# wrt54_relay_board.net
KiCad netlist of a schematic drawn in EAGLE
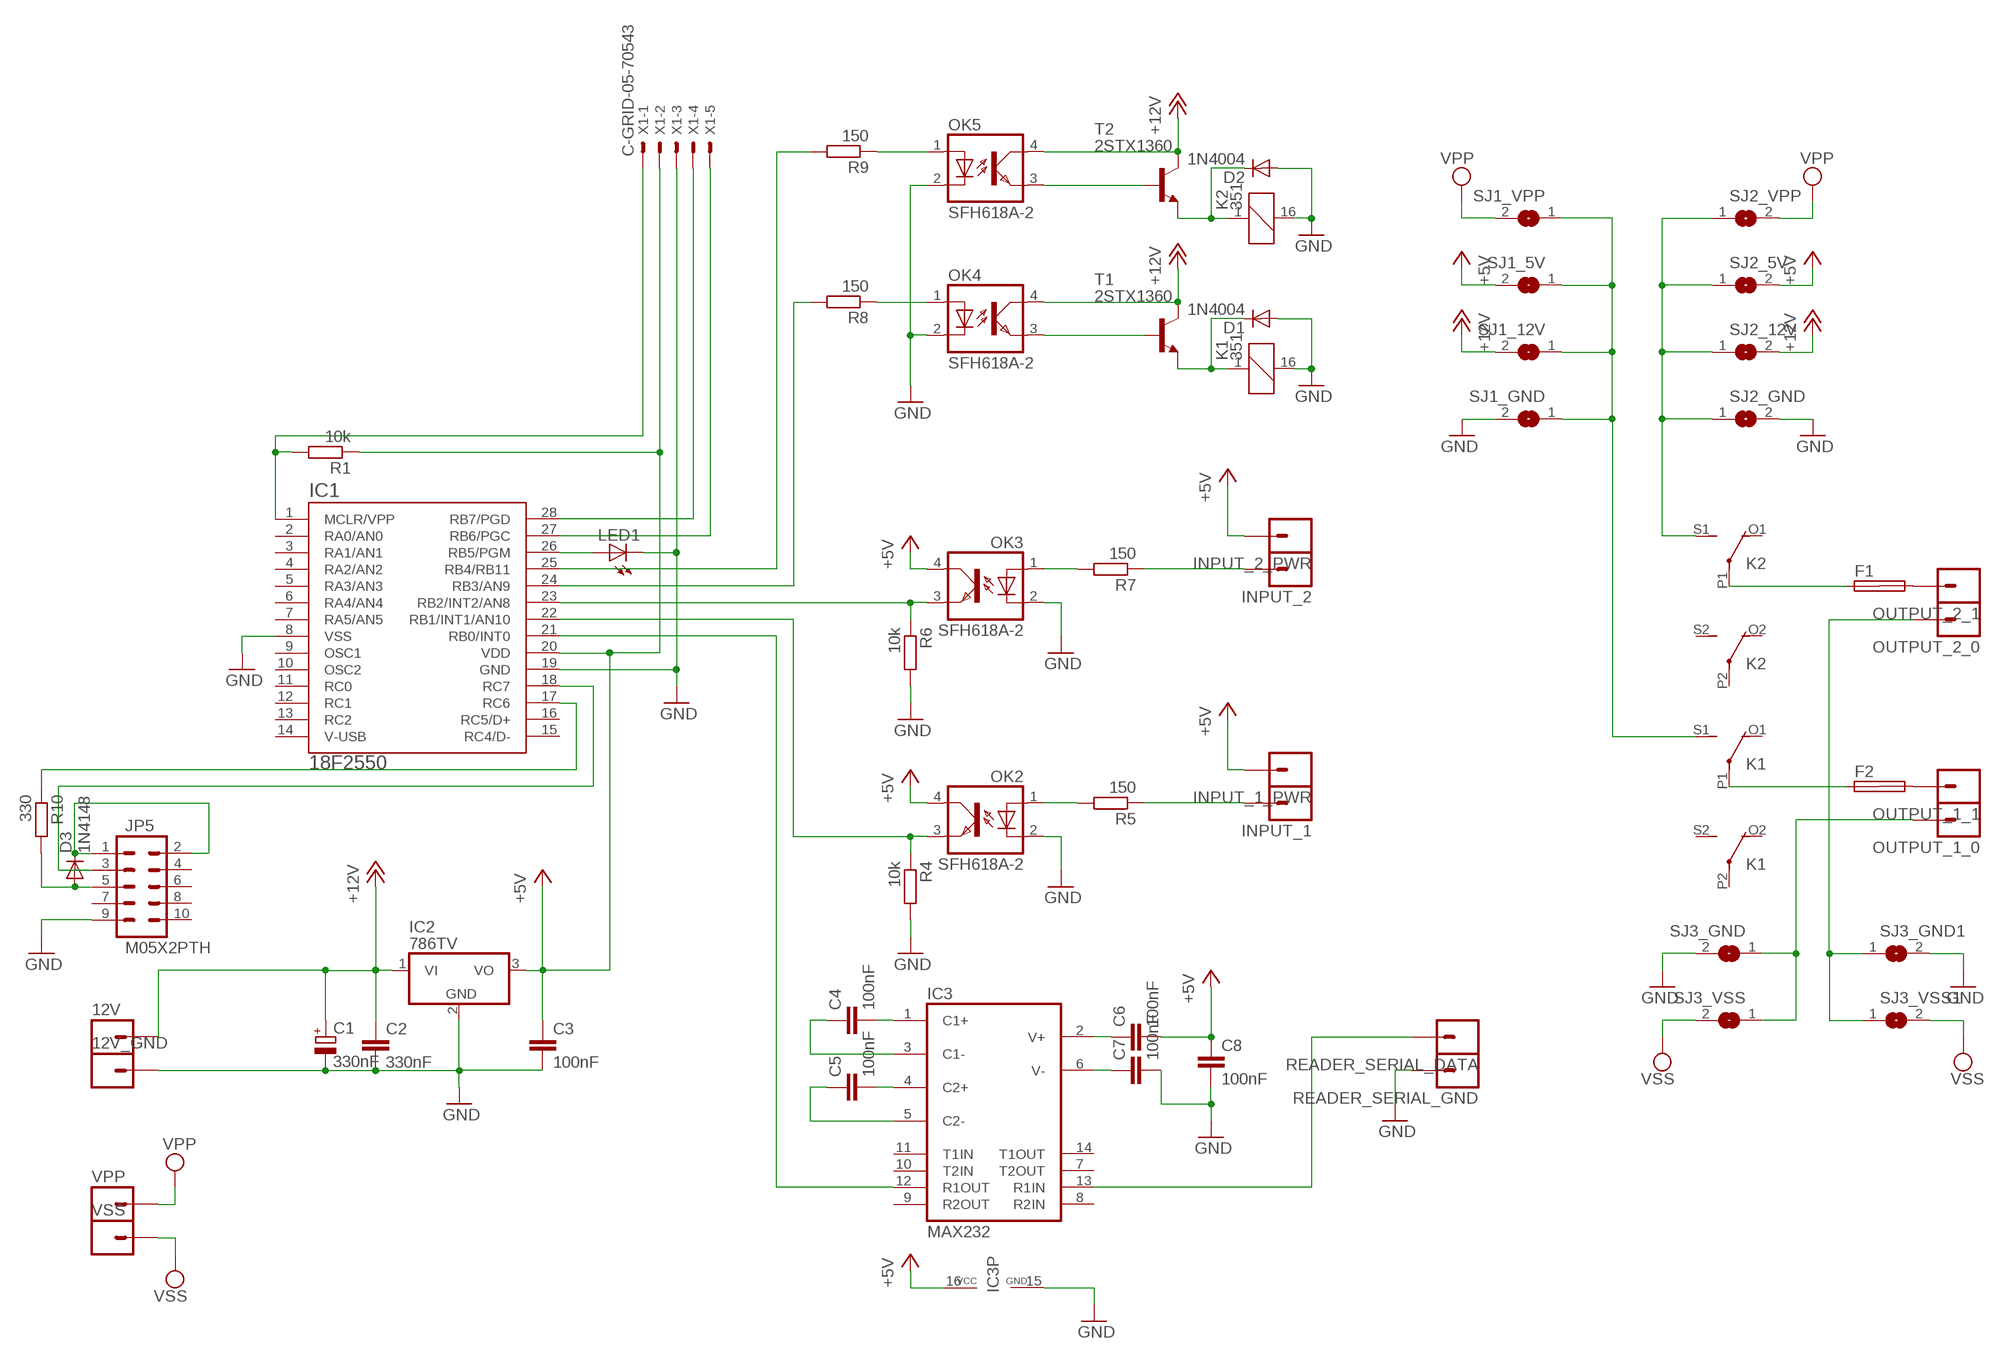
[diagram p0: schematic, sheet 1]

(export (version "E")
  (design (tool "Eeschema 10.0.6"))
  (components
    (comp (ref "12V")
      (value "M01PTH_LONGPAD")
      (footprint "eagle-import:1X01_LONGPAD")
      (libsource (lib "eagle-import") (part "M01PTH_LONGPAD"))
    )
    (comp (ref "12V_GND")
      (value "M01PTH_LONGPAD")
      (footprint "eagle-import:1X01_LONGPAD")
      (libsource (lib "eagle-import") (part "M01PTH_LONGPAD"))
    )
    (comp (ref "C1")
      (value "330nF")
      (footprint "eagle-import:E5-6")
      (libsource (lib "eagle-import") (part "CPOL-EUE5-6"))
    )
    (comp (ref "C2")
      (value "330nF")
      (footprint "eagle-import:C5B2.5")
      (libsource (lib "eagle-import") (part "C5/2.5"))
    )
    (comp (ref "C3")
      (value "100nF")
      (footprint "eagle-import:C5B2.5")
      (libsource (lib "eagle-import") (part "C5/2.5"))
    )
    (comp (ref "C4")
      (value "100nF")
      (footprint "eagle-import:C5B2.5")
      (libsource (lib "eagle-import") (part "C5/2.5"))
    )
    (comp (ref "C5")
      (value "100nF")
      (footprint "eagle-import:C5B2.5")
      (libsource (lib "eagle-import") (part "C5/2.5"))
    )
    (comp (ref "C6")
      (value "100nF")
      (footprint "eagle-import:C5B2.5")
      (libsource (lib "eagle-import") (part "C5/2.5"))
    )
    (comp (ref "C7")
      (value "100nF")
      (footprint "eagle-import:C5B2.5")
      (libsource (lib "eagle-import") (part "C5/2.5"))
    )
    (comp (ref "C8")
      (value "100nF")
      (footprint "eagle-import:C5B2.5")
      (libsource (lib "eagle-import") (part "C5/2.5"))
    )
    (comp (ref "D1")
      (value "1N4004")
      (footprint "eagle-import:DO35-7")
      (libsource (lib "eagle-import") (part "1N4148DO35-7"))
    )
    (comp (ref "D2")
      (value "1N4004")
      (footprint "eagle-import:DO35-7")
      (libsource (lib "eagle-import") (part "1N4148DO35-7"))
    )
    (comp (ref "D3")
      (value "1N4148")
      (footprint "eagle-import:DO35-7")
      (libsource (lib "eagle-import") (part "1N4148DO35-7"))
    )
    (comp (ref "F1")
      (value "SHK20L")
      (footprint "eagle-import:SHK20L")
      (libsource (lib "eagle-import") (part "SHK20L"))
    )
    (comp (ref "F2")
      (value "SHK20L")
      (footprint "eagle-import:SHK20L")
      (libsource (lib "eagle-import") (part "SHK20L"))
    )
    (comp (ref "IC1")
      (value "18F2550")
      (footprint "eagle-import:DIL28")
      (libsource (lib "eagle-import") (part "PIC18F2550DIL-28"))
    )
    (comp (ref "IC2")
      (value "786TV")
      (footprint "eagle-import:TO220V")
      (libsource (lib "eagle-import") (part "78TV6"))
    )
    (comp (ref "IC3")
      (value "MAX232")
      (footprint "eagle-import:DIL16")
      (fields (field (name "MF") "MAXIM") (field (name "MPN") "MAX232ACPE+"))
      (libsource (lib "eagle-import") (part "MAX232"))
    )
    (comp (ref "INPUT_1")
      (value "M01PTH_LONGPAD")
      (footprint "eagle-import:1X01_LONGPAD")
      (libsource (lib "eagle-import") (part "M01PTH_LONGPAD"))
    )
    (comp (ref "INPUT_1_PWR")
      (value "M01PTH_LONGPAD")
      (footprint "eagle-import:1X01_LONGPAD")
      (libsource (lib "eagle-import") (part "M01PTH_LONGPAD"))
    )
    (comp (ref "INPUT_2")
      (value "M01PTH_LONGPAD")
      (footprint "eagle-import:1X01_LONGPAD")
      (libsource (lib "eagle-import") (part "M01PTH_LONGPAD"))
    )
    (comp (ref "INPUT_2_PWR")
      (value "M01PTH_LONGPAD")
      (footprint "eagle-import:1X01_LONGPAD")
      (libsource (lib "eagle-import") (part "M01PTH_LONGPAD"))
    )
    (comp (ref "JP5")
      (value "M05X2PTH")
      (footprint "eagle-import:AVR_ICSP")
      (libsource (lib "eagle-import") (part "M05X2PTH"))
    )
    (comp (ref "K1")
      (value "351")
      (footprint "eagle-import:351")
      (libsource (lib "eagle-import") (part "351"))
    )
    (comp (ref "K2")
      (value "351")
      (footprint "eagle-import:351")
      (libsource (lib "eagle-import") (part "351"))
    )
    (comp (ref "LED1")
      (value "LED5MM")
      (footprint "eagle-import:LED5MM")
      (libsource (lib "eagle-import") (part "LED5MM"))
    )
    (comp (ref "OK2")
      (value "SFH618A-2")
      (footprint "eagle-import:DIP4")
      (libsource (lib "eagle-import") (part "SFH618?A-2"))
    )
    (comp (ref "OK3")
      (value "SFH618A-2")
      (footprint "eagle-import:DIP4")
      (libsource (lib "eagle-import") (part "SFH618?A-2"))
    )
    (comp (ref "OK4")
      (value "SFH618A-2")
      (footprint "eagle-import:DIP4")
      (libsource (lib "eagle-import") (part "SFH618?A-2"))
    )
    (comp (ref "OK5")
      (value "SFH618A-2")
      (footprint "eagle-import:DIP4")
      (libsource (lib "eagle-import") (part "SFH618?A-2"))
    )
    (comp (ref "OUTPUT_1_0")
      (value "M01PTH_LONGPAD")
      (footprint "eagle-import:1X01_LONGPAD")
      (libsource (lib "eagle-import") (part "M01PTH_LONGPAD"))
    )
    (comp (ref "OUTPUT_1_1")
      (value "M01PTH_LONGPAD")
      (footprint "eagle-import:1X01_LONGPAD")
      (libsource (lib "eagle-import") (part "M01PTH_LONGPAD"))
    )
    (comp (ref "OUTPUT_2_0")
      (value "M01PTH_LONGPAD")
      (footprint "eagle-import:1X01_LONGPAD")
      (libsource (lib "eagle-import") (part "M01PTH_LONGPAD"))
    )
    (comp (ref "OUTPUT_2_1")
      (value "M01PTH_LONGPAD")
      (footprint "eagle-import:1X01_LONGPAD")
      (libsource (lib "eagle-import") (part "M01PTH_LONGPAD"))
    )
    (comp (ref "R1")
      (value "10k")
      (footprint "eagle-import:0204_7")
      (libsource (lib "eagle-import") (part "R-EU_0204/7"))
    )
    (comp (ref "R4")
      (value "10k")
      (footprint "eagle-import:0207_10")
      (libsource (lib "eagle-import") (part "R-EU_0207/10"))
    )
    (comp (ref "R5")
      (value "150")
      (footprint "eagle-import:0204V")
      (libsource (lib "eagle-import") (part "R-EU_0204/2V"))
    )
    (comp (ref "R6")
      (value "10k")
      (footprint "eagle-import:0207_10")
      (libsource (lib "eagle-import") (part "R-EU_0207/10"))
    )
    (comp (ref "R7")
      (value "150")
      (footprint "eagle-import:0204V")
      (libsource (lib "eagle-import") (part "R-EU_0204/2V"))
    )
    (comp (ref "R8")
      (value "150")
      (footprint "eagle-import:0204_7")
      (libsource (lib "eagle-import") (part "R-EU_0204/7"))
    )
    (comp (ref "R9")
      (value "150")
      (footprint "eagle-import:0204_7")
      (libsource (lib "eagle-import") (part "R-EU_0204/7"))
    )
    (comp (ref "R10")
      (value "330")
      (footprint "eagle-import:0204V")
      (libsource (lib "eagle-import") (part "R-EU_0204/2V"))
    )
    (comp (ref "READER_SERIAL_DATA")
      (value "M01PTH_LONGPAD")
      (footprint "eagle-import:1X01_LONGPAD")
      (libsource (lib "eagle-import") (part "M01PTH_LONGPAD"))
    )
    (comp (ref "READER_SERIAL_GND")
      (value "M01PTH_LONGPAD")
      (footprint "eagle-import:1X01_LONGPAD")
      (libsource (lib "eagle-import") (part "M01PTH_LONGPAD"))
    )
    (comp (ref "SJ1_5V")
      (value "SJW")
      (footprint "eagle-import:SJW")
      (libsource (lib "eagle-import") (part "SJW"))
    )
    (comp (ref "SJ1_12V")
      (value "SJW")
      (footprint "eagle-import:SJW")
      (libsource (lib "eagle-import") (part "SJW"))
    )
    (comp (ref "SJ1_GND")
      (value "SJW")
      (footprint "eagle-import:SJW")
      (libsource (lib "eagle-import") (part "SJW"))
    )
    (comp (ref "SJ1_VPP")
      (value "SJW")
      (footprint "eagle-import:SJW")
      (libsource (lib "eagle-import") (part "SJW"))
    )
    (comp (ref "SJ2_5V")
      (value "SJW")
      (footprint "eagle-import:SJW")
      (libsource (lib "eagle-import") (part "SJW"))
    )
    (comp (ref "SJ2_12V")
      (value "SJW")
      (footprint "eagle-import:SJW")
      (libsource (lib "eagle-import") (part "SJW"))
    )
    (comp (ref "SJ2_GND")
      (value "SJW")
      (footprint "eagle-import:SJW")
      (libsource (lib "eagle-import") (part "SJW"))
    )
    (comp (ref "SJ2_VPP")
      (value "SJW")
      (footprint "eagle-import:SJW")
      (libsource (lib "eagle-import") (part "SJW"))
    )
    (comp (ref "SJ3_GND")
      (value "SJW")
      (footprint "eagle-import:SJW")
      (libsource (lib "eagle-import") (part "SJW"))
    )
    (comp (ref "SJ3_GND1")
      (value "SJW")
      (footprint "eagle-import:SJW")
      (libsource (lib "eagle-import") (part "SJW"))
    )
    (comp (ref "SJ3_VSS")
      (value "SJW")
      (footprint "eagle-import:SJW")
      (libsource (lib "eagle-import") (part "SJW"))
    )
    (comp (ref "SJ3_VSS1")
      (value "SJW")
      (footprint "eagle-import:SJW")
      (libsource (lib "eagle-import") (part "SJW"))
    )
    (comp (ref "T1")
      (value "2STX1360")
      (footprint "eagle-import:TO92-ECB")
      (libsource (lib "eagle-import") (part "2SC1740"))
    )
    (comp (ref "T2")
      (value "2STX1360")
      (footprint "eagle-import:TO92-ECB")
      (libsource (lib "eagle-import") (part "2SC1740"))
    )
    (comp (ref "VPP")
      (value "M01PTH_LONGPAD")
      (footprint "eagle-import:1X01_LONGPAD")
      (libsource (lib "eagle-import") (part "M01PTH_LONGPAD"))
    )
    (comp (ref "VSS")
      (value "M01PTH_LONGPAD")
      (footprint "eagle-import:1X01_LONGPAD")
      (libsource (lib "eagle-import") (part "M01PTH_LONGPAD"))
    )
    (comp (ref "X1")
      (value "C-GRID-05-70543")
      (footprint "eagle-import:70543-05")
      (libsource (lib "eagle-import") (part "C-GRID-05-70543"))
    )
  )
  (nets
    (net (code "1") (name "+5V") (class "Default")
      (node (ref "C3") (pin "1") (pinfunction "1_1") (pintype "passive"))
      (node (ref "C6") (pin "2") (pinfunction "2_2") (pintype "passive"))
      (node (ref "C8") (pin "1") (pinfunction "1_1") (pintype "passive"))
      (node (ref "IC1") (pin "20") (pinfunction "VDD_20") (pintype "bidirectional"))
      (node (ref "IC2") (pin "3") (pinfunction "VO_3") (pintype "passive"))
      (node (ref "IC3") (pin "16") (pinfunction "VCC_16") (pintype "power_in"))
      (node (ref "INPUT_1_PWR") (pin "1") (pinfunction "1_1") (pintype "passive"))
      (node (ref "INPUT_2_PWR") (pin "1") (pinfunction "1_1") (pintype "passive"))
      (node (ref "OK2") (pin "4") (pinfunction "COL_4") (pintype "passive"))
      (node (ref "OK3") (pin "4") (pinfunction "COL_4") (pintype "passive"))
      (node (ref "R1") (pin "1") (pinfunction "1_1") (pintype "passive"))
      (node (ref "SJ1_5V") (pin "2") (pinfunction "2_2") (pintype "passive"))
      (node (ref "SJ2_5V") (pin "2") (pinfunction "2_2") (pintype "passive"))
      (node (ref "X1") (pin "2") (pinfunction "S_2") (pintype "passive"))
    )
    (net (code "2") (name "+12V") (class "Default")
      (node (ref "12V") (pin "1") (pinfunction "1_1") (pintype "passive"))
      (node (ref "C1") (pin "+") (pinfunction "+_+") (pintype "passive"))
      (node (ref "C2") (pin "1") (pinfunction "1_1") (pintype "passive"))
      (node (ref "IC2") (pin "1") (pinfunction "VI_1") (pintype "input"))
      (node (ref "OK4") (pin "4") (pinfunction "COL_4") (pintype "passive"))
      (node (ref "OK5") (pin "4") (pinfunction "COL_4") (pintype "passive"))
      (node (ref "SJ1_12V") (pin "2") (pinfunction "2_2") (pintype "passive"))
      (node (ref "SJ2_12V") (pin "2") (pinfunction "2_2") (pintype "passive"))
      (node (ref "T1") (pin "C") (pinfunction "C_C") (pintype "passive"))
      (node (ref "T2") (pin "C") (pinfunction "C_C") (pintype "passive"))
    )
    (net (code "3") (name "GND") (class "Default")
      (node (ref "12V_GND") (pin "1") (pinfunction "1_1") (pintype "passive"))
      (node (ref "C1") (pin "-") (pinfunction "-_-") (pintype "passive"))
      (node (ref "C2") (pin "2") (pinfunction "2_2") (pintype "passive"))
      (node (ref "C3") (pin "2") (pinfunction "2_2") (pintype "passive"))
      (node (ref "C7") (pin "2") (pinfunction "2_2") (pintype "passive"))
      (node (ref "C8") (pin "2") (pinfunction "2_2") (pintype "passive"))
      (node (ref "D1") (pin "A") (pinfunction "A_A") (pintype "passive"))
      (node (ref "D2") (pin "A") (pinfunction "A_A") (pintype "passive"))
      (node (ref "IC1") (pin "19") (pinfunction "GND_19") (pintype "bidirectional"))
      (node (ref "IC1") (pin "8") (pinfunction "VSS_8") (pintype "bidirectional"))
      (node (ref "IC2") (pin "2") (pinfunction "GND_2") (pintype "passive"))
      (node (ref "IC3") (pin "15") (pinfunction "GND_15") (pintype "power_in"))
      (node (ref "JP5") (pin "9") (pinfunction "9_9") (pintype "passive"))
      (node (ref "K1") (pin "16") (pinfunction "2_16") (pintype "passive"))
      (node (ref "K2") (pin "16") (pinfunction "2_16") (pintype "passive"))
      (node (ref "LED1") (pin "K") (pinfunction "C_K") (pintype "passive"))
      (node (ref "OK2") (pin "2") (pinfunction "C_2") (pintype "passive"))
      (node (ref "OK3") (pin "2") (pinfunction "C_2") (pintype "passive"))
      (node (ref "OK4") (pin "2") (pinfunction "C_2") (pintype "passive"))
      (node (ref "OK5") (pin "2") (pinfunction "C_2") (pintype "passive"))
      (node (ref "R4") (pin "2") (pinfunction "2_2") (pintype "passive"))
      (node (ref "R6") (pin "2") (pinfunction "2_2") (pintype "passive"))
      (node (ref "READER_SERIAL_GND") (pin "1") (pinfunction "1_1") (pintype "passive"))
      (node (ref "SJ1_GND") (pin "2") (pinfunction "2_2") (pintype "passive"))
      (node (ref "SJ2_GND") (pin "2") (pinfunction "2_2") (pintype "passive"))
      (node (ref "SJ3_GND") (pin "2") (pinfunction "2_2") (pintype "passive"))
      (node (ref "SJ3_GND1") (pin "2") (pinfunction "2_2") (pintype "passive"))
      (node (ref "X1") (pin "3") (pinfunction "S_3") (pintype "passive"))
    )
    (net (code "4") (name "Net-(D1-PadC)") (class "Default")
      (node (ref "D1") (pin "C") (pinfunction "C_C") (pintype "passive"))
      (node (ref "K1") (pin "1") (pinfunction "1_1") (pintype "passive"))
      (node (ref "T1") (pin "E") (pinfunction "E_E") (pintype "passive"))
    )
    (net (code "5") (name "Net-(D2-PadC)") (class "Default")
      (node (ref "D2") (pin "C") (pinfunction "C_C") (pintype "passive"))
      (node (ref "K2") (pin "1") (pinfunction "1_1") (pintype "passive"))
      (node (ref "T2") (pin "E") (pinfunction "E_E") (pintype "passive"))
    )
    (net (code "6") (name "Net-(D3-PadA)") (class "Default")
      (node (ref "D3") (pin "A") (pinfunction "A_A") (pintype "passive"))
      (node (ref "JP5") (pin "5") (pinfunction "5_5") (pintype "passive"))
      (node (ref "R10") (pin "2") (pinfunction "2_2") (pintype "passive"))
    )
    (net (code "7") (name "Net-(D3-PadC)") (class "Default")
      (node (ref "D3") (pin "C") (pinfunction "C_C") (pintype "passive"))
      (node (ref "JP5") (pin "1") (pinfunction "1_1") (pintype "passive"))
      (node (ref "JP5") (pin "2") (pinfunction "2_2") (pintype "passive"))
    )
    (net (code "8") (name "Net-(F1-Pad2A)") (class "Default")
      (node (ref "F1") (pin "2A") (pinfunction "2A_2A") (pintype "passive"))
      (node (ref "OUTPUT_2_1") (pin "1") (pinfunction "1_1") (pintype "passive"))
    )
    (net (code "9") (name "Net-(F2-Pad2A)") (class "Default")
      (node (ref "F2") (pin "2A") (pinfunction "2A_2A") (pintype "passive"))
      (node (ref "OUTPUT_1_1") (pin "1") (pinfunction "1_1") (pintype "passive"))
    )
    (net (code "10") (name "Net-(IC1-MCLR{slash}VPP)") (class "Default")
      (node (ref "IC1") (pin "1") (pinfunction "MCLR/VPP_1") (pintype "bidirectional"))
      (node (ref "R1") (pin "2") (pinfunction "2_2") (pintype "passive"))
      (node (ref "X1") (pin "1") (pinfunction "S_1") (pintype "passive"))
    )
    (net (code "11") (name "Net-(IC1-RB0{slash}INT0)") (class "Default")
      (node (ref "IC1") (pin "21") (pinfunction "RB0/INT0_21") (pintype "bidirectional"))
      (node (ref "IC3") (pin "12") (pinfunction "R1OUT_12") (pintype "output"))
    )
    (net (code "12") (name "Net-(IC1-RB1{slash}INT1{slash}AN10)") (class "Default")
      (node (ref "IC1") (pin "22") (pinfunction "RB1/INT1/AN10_22") (pintype "bidirectional"))
      (node (ref "OK2") (pin "3") (pinfunction "EMIT_3") (pintype "passive"))
      (node (ref "R4") (pin "1") (pinfunction "1_1") (pintype "passive"))
    )
    (net (code "13") (name "Net-(IC1-RB2{slash}INT2{slash}AN8)") (class "Default")
      (node (ref "IC1") (pin "23") (pinfunction "RB2/INT2/AN8_23") (pintype "bidirectional"))
      (node (ref "OK3") (pin "3") (pinfunction "EMIT_3") (pintype "passive"))
      (node (ref "R6") (pin "1") (pinfunction "1_1") (pintype "passive"))
    )
    (net (code "14") (name "Net-(IC1-RB3{slash}AN9)") (class "Default")
      (node (ref "IC1") (pin "24") (pinfunction "RB3/AN9_24") (pintype "bidirectional"))
      (node (ref "R8") (pin "2") (pinfunction "2_2") (pintype "passive"))
    )
    (net (code "15") (name "Net-(IC1-RB4{slash}RB11)") (class "Default")
      (node (ref "IC1") (pin "25") (pinfunction "RB4/RB11_25") (pintype "bidirectional"))
      (node (ref "R9") (pin "2") (pinfunction "2_2") (pintype "passive"))
    )
    (net (code "16") (name "Net-(IC1-RB5{slash}PGM)") (class "Default")
      (node (ref "IC1") (pin "26") (pinfunction "RB5/PGM_26") (pintype "bidirectional"))
      (node (ref "LED1") (pin "A") (pinfunction "A_A") (pintype "passive"))
    )
    (net (code "17") (name "Net-(IC1-RB6{slash}PGC)") (class "Default")
      (node (ref "IC1") (pin "27") (pinfunction "RB6/PGC_27") (pintype "bidirectional"))
      (node (ref "X1") (pin "5") (pinfunction "S_5") (pintype "passive"))
    )
    (net (code "18") (name "Net-(IC1-RB7{slash}PGD)") (class "Default")
      (node (ref "IC1") (pin "28") (pinfunction "RB7/PGD_28") (pintype "bidirectional"))
      (node (ref "X1") (pin "4") (pinfunction "S_4") (pintype "passive"))
    )
    (net (code "19") (name "Net-(IC1-RC6)") (class "Default")
      (node (ref "IC1") (pin "17") (pinfunction "RC6_17") (pintype "bidirectional"))
      (node (ref "R10") (pin "1") (pinfunction "1_1") (pintype "passive"))
    )
    (net (code "20") (name "Net-(IC1-RC7)") (class "Default")
      (node (ref "IC1") (pin "18") (pinfunction "RC7_18") (pintype "bidirectional"))
      (node (ref "JP5") (pin "3") (pinfunction "3_3") (pintype "passive"))
    )
    (net (code "21") (name "Net-(IC3A-C1+)") (class "Default")
      (node (ref "C4") (pin "2") (pinfunction "2_2") (pintype "passive"))
      (node (ref "IC3") (pin "1") (pinfunction "C1+_1") (pintype "bidirectional"))
    )
    (net (code "22") (name "Net-(IC3A-C1-)") (class "Default")
      (node (ref "C4") (pin "1") (pinfunction "1_1") (pintype "passive"))
      (node (ref "IC3") (pin "3") (pinfunction "C1-_3") (pintype "bidirectional"))
    )
    (net (code "23") (name "Net-(IC3A-C2+)") (class "Default")
      (node (ref "C5") (pin "2") (pinfunction "2_2") (pintype "passive"))
      (node (ref "IC3") (pin "4") (pinfunction "C2+_4") (pintype "bidirectional"))
    )
    (net (code "24") (name "Net-(IC3A-C2-)") (class "Default")
      (node (ref "C5") (pin "1") (pinfunction "1_1") (pintype "passive"))
      (node (ref "IC3") (pin "5") (pinfunction "C2-_5") (pintype "bidirectional"))
    )
    (net (code "25") (name "Net-(IC3A-R1IN)") (class "Default")
      (node (ref "IC3") (pin "13") (pinfunction "R1IN_13") (pintype "input"))
      (node (ref "READER_SERIAL_DATA") (pin "1") (pinfunction "1_1") (pintype "passive"))
    )
    (net (code "26") (name "Net-(IC3A-V+)") (class "Default")
      (node (ref "C6") (pin "1") (pinfunction "1_1") (pintype "passive"))
      (node (ref "IC3") (pin "2") (pinfunction "V+_2") (pintype "bidirectional"))
    )
    (net (code "27") (name "Net-(IC3A-V-)") (class "Default")
      (node (ref "C7") (pin "1") (pinfunction "1_1") (pintype "passive"))
      (node (ref "IC3") (pin "6") (pinfunction "V-_6") (pintype "bidirectional"))
    )
    (net (code "28") (name "Net-(INPUT_1-Pad1)") (class "Default")
      (node (ref "INPUT_1") (pin "1") (pinfunction "1_1") (pintype "passive"))
      (node (ref "R5") (pin "1") (pinfunction "1_1") (pintype "passive"))
    )
    (net (code "29") (name "Net-(INPUT_2-Pad1)") (class "Default")
      (node (ref "INPUT_2") (pin "1") (pinfunction "1_1") (pintype "passive"))
      (node (ref "R7") (pin "1") (pinfunction "1_1") (pintype "passive"))
    )
    (net (code "30") (name "Net-(K1B-P)") (class "Default")
      (node (ref "F2") (pin "1A") (pinfunction "1A_1A") (pintype "passive"))
      (node (ref "K1") (pin "P1") (pinfunction "P_P1") (pintype "passive"))
    )
    (net (code "31") (name "Net-(K1B-S)") (class "Default")
      (node (ref "K1") (pin "S1") (pinfunction "S_S1") (pintype "passive"))
      (node (ref "SJ1_12V") (pin "1") (pinfunction "1_1") (pintype "passive"))
      (node (ref "SJ1_5V") (pin "1") (pinfunction "1_1") (pintype "passive"))
      (node (ref "SJ1_GND") (pin "1") (pinfunction "1_1") (pintype "passive"))
      (node (ref "SJ1_VPP") (pin "1") (pinfunction "1_1") (pintype "passive"))
    )
    (net (code "32") (name "Net-(K2B-P)") (class "Default")
      (node (ref "F1") (pin "1A") (pinfunction "1A_1A") (pintype "passive"))
      (node (ref "K2") (pin "P1") (pinfunction "P_P1") (pintype "passive"))
    )
    (net (code "33") (name "Net-(K2B-S)") (class "Default")
      (node (ref "K2") (pin "S1") (pinfunction "S_S1") (pintype "passive"))
      (node (ref "SJ2_12V") (pin "1") (pinfunction "1_1") (pintype "passive"))
      (node (ref "SJ2_5V") (pin "1") (pinfunction "1_1") (pintype "passive"))
      (node (ref "SJ2_GND") (pin "1") (pinfunction "1_1") (pintype "passive"))
      (node (ref "SJ2_VPP") (pin "1") (pinfunction "1_1") (pintype "passive"))
    )
    (net (code "34") (name "Net-(OK2-A)") (class "Default")
      (node (ref "OK2") (pin "1") (pinfunction "A_1") (pintype "passive"))
      (node (ref "R5") (pin "2") (pinfunction "2_2") (pintype "passive"))
    )
    (net (code "35") (name "Net-(OK3-A)") (class "Default")
      (node (ref "OK3") (pin "1") (pinfunction "A_1") (pintype "passive"))
      (node (ref "R7") (pin "2") (pinfunction "2_2") (pintype "passive"))
    )
    (net (code "36") (name "Net-(OK4-A)") (class "Default")
      (node (ref "OK4") (pin "1") (pinfunction "A_1") (pintype "passive"))
      (node (ref "R8") (pin "1") (pinfunction "1_1") (pintype "passive"))
    )
    (net (code "37") (name "Net-(OK4-EMIT)") (class "Default")
      (node (ref "OK4") (pin "3") (pinfunction "EMIT_3") (pintype "passive"))
      (node (ref "T1") (pin "B") (pinfunction "B_B") (pintype "passive"))
    )
    (net (code "38") (name "Net-(OK5-A)") (class "Default")
      (node (ref "OK5") (pin "1") (pinfunction "A_1") (pintype "passive"))
      (node (ref "R9") (pin "1") (pinfunction "1_1") (pintype "passive"))
    )
    (net (code "39") (name "Net-(OK5-EMIT)") (class "Default")
      (node (ref "OK5") (pin "3") (pinfunction "EMIT_3") (pintype "passive"))
      (node (ref "T2") (pin "B") (pinfunction "B_B") (pintype "passive"))
    )
    (net (code "40") (name "Net-(OUTPUT_1_0-Pad1)") (class "Default")
      (node (ref "OUTPUT_1_0") (pin "1") (pinfunction "1_1") (pintype "passive"))
      (node (ref "SJ3_GND") (pin "1") (pinfunction "1_1") (pintype "passive"))
      (node (ref "SJ3_VSS") (pin "1") (pinfunction "1_1") (pintype "passive"))
    )
    (net (code "41") (name "Net-(OUTPUT_2_0-Pad1)") (class "Default")
      (node (ref "OUTPUT_2_0") (pin "1") (pinfunction "1_1") (pintype "passive"))
      (node (ref "SJ3_GND1") (pin "1") (pinfunction "1_1") (pintype "passive"))
      (node (ref "SJ3_VSS1") (pin "1") (pinfunction "1_1") (pintype "passive"))
    )
    (net (code "42") (name "VPP") (class "Default")
      (node (ref "SJ1_VPP") (pin "2") (pinfunction "2_2") (pintype "passive"))
      (node (ref "SJ2_VPP") (pin "2") (pinfunction "2_2") (pintype "passive"))
      (node (ref "VPP") (pin "1") (pinfunction "1_1") (pintype "passive"))
    )
    (net (code "43") (name "VSS") (class "Default")
      (node (ref "SJ3_VSS") (pin "2") (pinfunction "2_2") (pintype "passive"))
      (node (ref "SJ3_VSS1") (pin "2") (pinfunction "2_2") (pintype "passive"))
      (node (ref "VSS") (pin "1") (pinfunction "1_1") (pintype "passive"))
    )
    (net (code "44") (name "unconnected-(F1-Pad1B)") (class "Default")
      (node (ref "F1") (pin "1B") (pinfunction "1B_1B") (pintype "passive"))
    )
    (net (code "45") (name "unconnected-(F1-Pad2B)") (class "Default")
      (node (ref "F1") (pin "2B") (pinfunction "2B_2B") (pintype "passive"))
    )
    (net (code "46") (name "unconnected-(F2-Pad1B)") (class "Default")
      (node (ref "F2") (pin "1B") (pinfunction "1B_1B") (pintype "passive"))
    )
    (net (code "47") (name "unconnected-(F2-Pad2B)") (class "Default")
      (node (ref "F2") (pin "2B") (pinfunction "2B_2B") (pintype "passive"))
    )
    (net (code "48") (name "unconnected-(IC1-OSC1-Pad9)") (class "Default")
      (node (ref "IC1") (pin "9") (pinfunction "OSC1_9") (pintype "bidirectional"))
    )
    (net (code "49") (name "unconnected-(IC1-OSC2-Pad10)") (class "Default")
      (node (ref "IC1") (pin "10") (pinfunction "OSC2_10") (pintype "bidirectional"))
    )
    (net (code "50") (name "unconnected-(IC1-RA0{slash}AN0-Pad2)") (class "Default")
      (node (ref "IC1") (pin "2") (pinfunction "RA0/AN0_2") (pintype "bidirectional"))
    )
    (net (code "51") (name "unconnected-(IC1-RA1{slash}AN1-Pad3)") (class "Default")
      (node (ref "IC1") (pin "3") (pinfunction "RA1/AN1_3") (pintype "bidirectional"))
    )
    (net (code "52") (name "unconnected-(IC1-RA2{slash}AN2-Pad4)") (class "Default")
      (node (ref "IC1") (pin "4") (pinfunction "RA2/AN2_4") (pintype "bidirectional"))
    )
    (net (code "53") (name "unconnected-(IC1-RA3{slash}AN3-Pad5)") (class "Default")
      (node (ref "IC1") (pin "5") (pinfunction "RA3/AN3_5") (pintype "bidirectional"))
    )
    (net (code "54") (name "unconnected-(IC1-RA4{slash}AN4-Pad6)") (class "Default")
      (node (ref "IC1") (pin "6") (pinfunction "RA4/AN4_6") (pintype "bidirectional"))
    )
    (net (code "55") (name "unconnected-(IC1-RA5{slash}AN5-Pad7)") (class "Default")
      (node (ref "IC1") (pin "7") (pinfunction "RA5/AN5_7") (pintype "bidirectional"))
    )
    (net (code "56") (name "unconnected-(IC1-RC0-Pad11)") (class "Default")
      (node (ref "IC1") (pin "11") (pinfunction "RC0_11") (pintype "bidirectional"))
    )
    (net (code "57") (name "unconnected-(IC1-RC1-Pad12)") (class "Default")
      (node (ref "IC1") (pin "12") (pinfunction "RC1_12") (pintype "bidirectional"))
    )
    (net (code "58") (name "unconnected-(IC1-RC2-Pad13)") (class "Default")
      (node (ref "IC1") (pin "13") (pinfunction "RC2_13") (pintype "bidirectional"))
    )
    (net (code "59") (name "unconnected-(IC1-RC4{slash}D--Pad15)") (class "Default")
      (node (ref "IC1") (pin "15") (pinfunction "RC4/D-_15") (pintype "bidirectional"))
    )
    (net (code "60") (name "unconnected-(IC1-RC5{slash}D+-Pad16)") (class "Default")
      (node (ref "IC1") (pin "16") (pinfunction "RC5/D+_16") (pintype "bidirectional"))
    )
    (net (code "61") (name "unconnected-(IC1-V-USB-Pad14)") (class "Default")
      (node (ref "IC1") (pin "14") (pinfunction "V-USB_14") (pintype "bidirectional"))
    )
    (net (code "62") (name "unconnected-(IC3A-R2IN-Pad8)") (class "Default")
      (node (ref "IC3") (pin "8") (pinfunction "R2IN_8") (pintype "input"))
    )
    (net (code "63") (name "unconnected-(IC3A-R2OUT-Pad9)") (class "Default")
      (node (ref "IC3") (pin "9") (pinfunction "R2OUT_9") (pintype "output"))
    )
    (net (code "64") (name "unconnected-(IC3A-T1IN-Pad11)") (class "Default")
      (node (ref "IC3") (pin "11") (pinfunction "T1IN_11") (pintype "input"))
    )
    (net (code "65") (name "unconnected-(IC3A-T1OUT-Pad14)") (class "Default")
      (node (ref "IC3") (pin "14") (pinfunction "T1OUT_14") (pintype "output"))
    )
    (net (code "66") (name "unconnected-(IC3A-T2IN-Pad10)") (class "Default")
      (node (ref "IC3") (pin "10") (pinfunction "T2IN_10") (pintype "input"))
    )
    (net (code "67") (name "unconnected-(IC3A-T2OUT-Pad7)") (class "Default")
      (node (ref "IC3") (pin "7") (pinfunction "T2OUT_7") (pintype "output"))
    )
    (net (code "68") (name "unconnected-(JP5-Pad4)") (class "Default")
      (node (ref "JP5") (pin "4") (pinfunction "4_4") (pintype "passive"))
    )
    (net (code "69") (name "unconnected-(JP5-Pad6)") (class "Default")
      (node (ref "JP5") (pin "6") (pinfunction "6_6") (pintype "passive"))
    )
    (net (code "70") (name "unconnected-(JP5-Pad7)") (class "Default")
      (node (ref "JP5") (pin "7") (pinfunction "7_7") (pintype "passive"))
    )
    (net (code "71") (name "unconnected-(JP5-Pad8)") (class "Default")
      (node (ref "JP5") (pin "8") (pinfunction "8_8") (pintype "passive"))
    )
    (net (code "72") (name "unconnected-(JP5-Pad10)") (class "Default")
      (node (ref "JP5") (pin "10") (pinfunction "10_10") (pintype "passive"))
    )
    (net (code "73") (name "unconnected-(K1B-O-PadO1)") (class "Default")
      (node (ref "K1") (pin "O1") (pinfunction "O_O1") (pintype "passive"))
    )
    (net (code "74") (name "unconnected-(K1C-O-PadO2)") (class "Default")
      (node (ref "K1") (pin "O2") (pinfunction "O_O2") (pintype "passive"))
    )
    (net (code "75") (name "unconnected-(K1C-P-PadP2)") (class "Default")
      (node (ref "K1") (pin "P2") (pinfunction "P_P2") (pintype "passive"))
    )
    (net (code "76") (name "unconnected-(K1C-S-PadS2)") (class "Default")
      (node (ref "K1") (pin "S2") (pinfunction "S_S2") (pintype "passive"))
    )
    (net (code "77") (name "unconnected-(K2B-O-PadO1)") (class "Default")
      (node (ref "K2") (pin "O1") (pinfunction "O_O1") (pintype "passive"))
    )
    (net (code "78") (name "unconnected-(K2C-O-PadO2)") (class "Default")
      (node (ref "K2") (pin "O2") (pinfunction "O_O2") (pintype "passive"))
    )
    (net (code "79") (name "unconnected-(K2C-P-PadP2)") (class "Default")
      (node (ref "K2") (pin "P2") (pinfunction "P_P2") (pintype "passive"))
    )
    (net (code "80") (name "unconnected-(K2C-S-PadS2)") (class "Default")
      (node (ref "K2") (pin "S2") (pinfunction "S_S2") (pintype "passive"))
    )
  )
)
